# rpi_ad7705-2.net
KiCad netlist of a schematic drawn in EAGLE
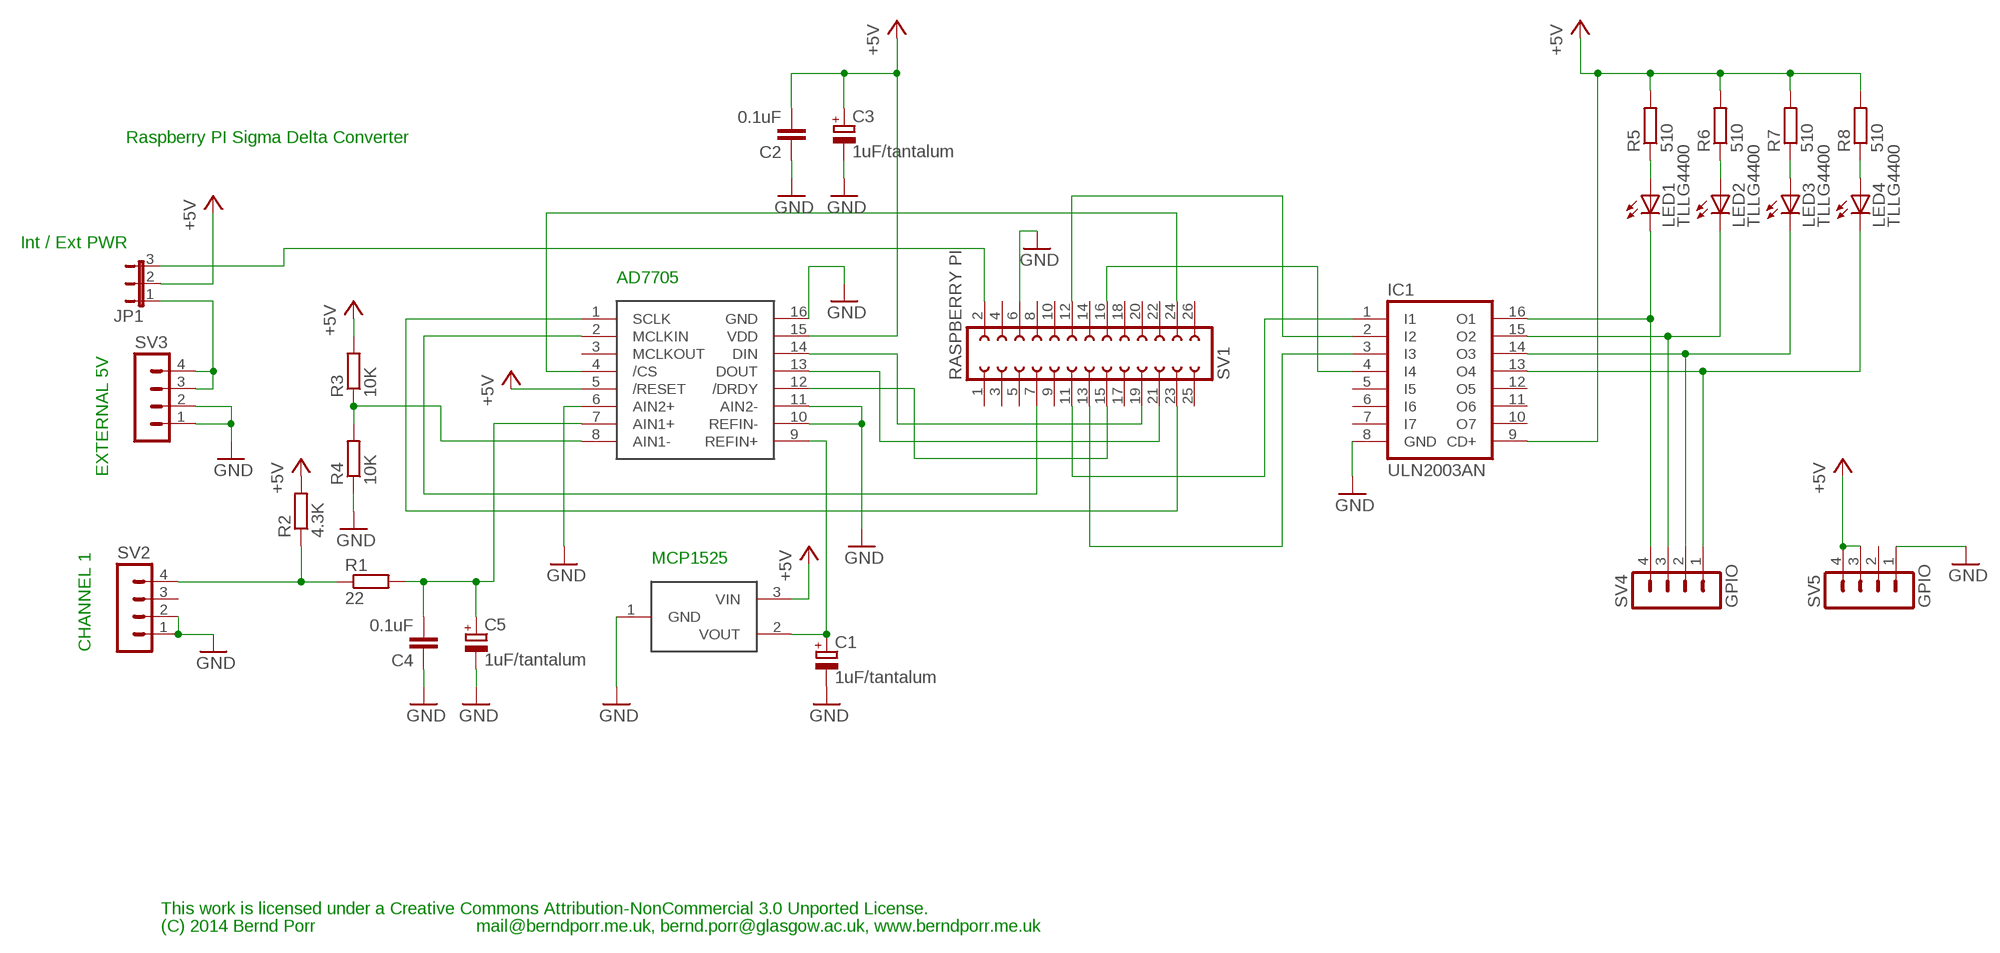
[diagram p0: schematic, sheet 1]

(export (version "E")
  (design (tool "Eeschema 10.0.6"))
  (components
    (comp (ref "C1")
      (value "1uF/tantalum")
      (footprint "eagle-import:TT2D7")
      (libsource (lib "eagle-import") (part "CPOL-EUTT2D7"))
    )
    (comp (ref "C2")
      (value "0.1uF")
      (footprint "eagle-import:C5B2.5")
      (libsource (lib "eagle-import") (part "C5/2.5"))
    )
    (comp (ref "C3")
      (value "1uF/tantalum")
      (footprint "eagle-import:TT2D7")
      (libsource (lib "eagle-import") (part "CPOL-EUTT2D7"))
    )
    (comp (ref "C4")
      (value "0.1uF")
      (footprint "eagle-import:C5B2.5")
      (libsource (lib "eagle-import") (part "C5/2.5"))
    )
    (comp (ref "C5")
      (value "1uF/tantalum")
      (footprint "eagle-import:TT2D7")
      (libsource (lib "eagle-import") (part "CPOL-EUTT2D7"))
    )
    (comp (ref "IC1")
      (value "ULN2003AN")
      (footprint "eagle-import:DIL16")
      (libsource (lib "eagle-import") (part "ULN2003AN"))
    )
    (comp (ref "JP1")
      (value "JP2E")
      (footprint "eagle-import:JP2")
      (libsource (lib "eagle-import") (part "JP2E"))
    )
    (comp (ref "LED1")
      (value "TLLG4400")
      (footprint "eagle-import:LED3MM")
      (fields (field (name "MF") "VISHAY SEMICONDUCTOR"))
      (libsource (lib "eagle-import") (part "TLLG4400"))
    )
    (comp (ref "LED2")
      (value "TLLG4400")
      (footprint "eagle-import:LED3MM")
      (fields (field (name "MF") "VISHAY SEMICONDUCTOR"))
      (libsource (lib "eagle-import") (part "TLLG4400"))
    )
    (comp (ref "LED3")
      (value "TLLG4400")
      (footprint "eagle-import:LED3MM")
      (fields (field (name "MF") "VISHAY SEMICONDUCTOR"))
      (libsource (lib "eagle-import") (part "TLLG4400"))
    )
    (comp (ref "LED4")
      (value "TLLG4400")
      (footprint "eagle-import:LED3MM")
      (fields (field (name "MF") "VISHAY SEMICONDUCTOR"))
      (libsource (lib "eagle-import") (part "TLLG4400"))
    )
    (comp (ref "R1")
      (value "22")
      (footprint "eagle-import:0207_10")
      (libsource (lib "eagle-import") (part "R-EU_0207/10"))
    )
    (comp (ref "R2")
      (value "4.3K")
      (footprint "eagle-import:0207_10")
      (libsource (lib "eagle-import") (part "R-EU_0207/10"))
    )
    (comp (ref "R3")
      (value "10K")
      (footprint "eagle-import:0207_10")
      (libsource (lib "eagle-import") (part "R-EU_0207/10"))
    )
    (comp (ref "R4")
      (value "10K")
      (footprint "eagle-import:0207_10")
      (libsource (lib "eagle-import") (part "R-EU_0207/10"))
    )
    (comp (ref "R5")
      (value "510")
      (footprint "eagle-import:0207_10")
      (libsource (lib "eagle-import") (part "R-EU_0207/10"))
    )
    (comp (ref "R6")
      (value "510")
      (footprint "eagle-import:0207_10")
      (libsource (lib "eagle-import") (part "R-EU_0207/10"))
    )
    (comp (ref "R7")
      (value "510")
      (footprint "eagle-import:0207_10")
      (libsource (lib "eagle-import") (part "R-EU_0207/10"))
    )
    (comp (ref "R8")
      (value "510")
      (footprint "eagle-import:0207_10")
      (libsource (lib "eagle-import") (part "R-EU_0207/10"))
    )
    (comp (ref "SV1")
      (value "RASPBERRY PI")
      (footprint "eagle-import:FE13-2")
      (libsource (lib "eagle-import") (part "FE13-2"))
    )
    (comp (ref "SV2")
      (value "MA04-1")
      (footprint "eagle-import:MA04-1")
      (libsource (lib "eagle-import") (part "MA04-1"))
    )
    (comp (ref "SV3")
      (value "MA04-1")
      (footprint "eagle-import:MA04-1")
      (libsource (lib "eagle-import") (part "MA04-1"))
    )
    (comp (ref "SV4")
      (value "GPIO")
      (footprint "eagle-import:MA04-1")
      (libsource (lib "eagle-import") (part "MA04-1"))
    )
    (comp (ref "SV5")
      (value "GPIO")
      (footprint "eagle-import:MA04-1")
      (libsource (lib "eagle-import") (part "MA04-1"))
    )
    (comp (ref "U$1")
      (value "AD7705")
      (footprint "eagle-import:DIP16")
      (libsource (lib "eagle-import") (part "AD7705"))
    )
    (comp (ref "U$2")
      (value "MCP1525")
      (footprint "eagle-import:TO92")
      (libsource (lib "eagle-import") (part "MCP1525"))
    )
  )
  (nets
    (net (code "1") (name "+5V") (class "Default")
      (node (ref "C2") (pin "2") (pinfunction "2_2") (pintype "passive"))
      (node (ref "C3") (pin "+") (pinfunction "+_+") (pintype "passive"))
      (node (ref "IC1") (pin "9") (pinfunction "CD+_9") (pintype "passive"))
      (node (ref "JP1") (pin "2") (pinfunction "2_2") (pintype "passive"))
      (node (ref "R2") (pin "2") (pinfunction "2_2") (pintype "passive"))
      (node (ref "R3") (pin "2") (pinfunction "2_2") (pintype "passive"))
      (node (ref "R5") (pin "2") (pinfunction "2_2") (pintype "passive"))
      (node (ref "R6") (pin "2") (pinfunction "2_2") (pintype "passive"))
      (node (ref "R7") (pin "2") (pinfunction "2_2") (pintype "passive"))
      (node (ref "R8") (pin "2") (pinfunction "2_2") (pintype "passive"))
      (node (ref "SV5") (pin "3") (pinfunction "3_3") (pintype "passive"))
      (node (ref "SV5") (pin "4") (pinfunction "4_4") (pintype "passive"))
      (node (ref "U$1") (pin "15") (pinfunction "VDD_15") (pintype "power_in"))
      (node (ref "U$1") (pin "5") (pinfunction "/RESET_5") (pintype "bidirectional"))
      (node (ref "U$2") (pin "3") (pinfunction "VIN_3") (pintype "power_in"))
    )
    (net (code "2") (name "GND") (class "Default")
      (node (ref "C1") (pin "-") (pinfunction "-_-") (pintype "passive"))
      (node (ref "C2") (pin "1") (pinfunction "1_1") (pintype "passive"))
      (node (ref "C3") (pin "-") (pinfunction "-_-") (pintype "passive"))
      (node (ref "C4") (pin "1") (pinfunction "1_1") (pintype "passive"))
      (node (ref "C5") (pin "-") (pinfunction "-_-") (pintype "passive"))
      (node (ref "IC1") (pin "8") (pinfunction "GND_8") (pintype "power_in"))
      (node (ref "R4") (pin "1") (pinfunction "1_1") (pintype "passive"))
      (node (ref "SV1") (pin "6") (pinfunction "6_6") (pintype "passive"))
      (node (ref "SV2") (pin "1") (pinfunction "1_1") (pintype "passive"))
      (node (ref "SV2") (pin "2") (pinfunction "2_2") (pintype "passive"))
      (node (ref "SV3") (pin "1") (pinfunction "1_1") (pintype "passive"))
      (node (ref "SV3") (pin "2") (pinfunction "2_2") (pintype "passive"))
      (node (ref "SV5") (pin "1") (pinfunction "1_1") (pintype "passive"))
      (node (ref "U$1") (pin "10") (pinfunction "REFIN-_10") (pintype "bidirectional"))
      (node (ref "U$1") (pin "11") (pinfunction "AIN2-_11") (pintype "bidirectional"))
      (node (ref "U$1") (pin "16") (pinfunction "GND_16") (pintype "power_in"))
      (node (ref "U$1") (pin "6") (pinfunction "AIN2+_6") (pintype "bidirectional"))
      (node (ref "U$2") (pin "1") (pinfunction "GND_1") (pintype "power_in"))
    )
    (net (code "3") (name "Net-(IC1-I1)") (class "Default")
      (node (ref "IC1") (pin "1") (pinfunction "I1_1") (pintype "input"))
      (node (ref "SV1") (pin "11") (pinfunction "11_11") (pintype "passive"))
    )
    (net (code "4") (name "Net-(IC1-I2)") (class "Default")
      (node (ref "IC1") (pin "2") (pinfunction "I2_2") (pintype "input"))
      (node (ref "SV1") (pin "12") (pinfunction "12_12") (pintype "passive"))
    )
    (net (code "5") (name "Net-(IC1-I3)") (class "Default")
      (node (ref "IC1") (pin "3") (pinfunction "I3_3") (pintype "input"))
      (node (ref "SV1") (pin "13") (pinfunction "13_13") (pintype "passive"))
    )
    (net (code "6") (name "Net-(IC1-I4)") (class "Default")
      (node (ref "IC1") (pin "4") (pinfunction "I4_4") (pintype "input"))
      (node (ref "SV1") (pin "16") (pinfunction "16_16") (pintype "passive"))
    )
    (net (code "7") (name "Net-(IC1-O1)") (class "Default")
      (node (ref "IC1") (pin "16") (pinfunction "O1_16") (pintype "open_collector"))
      (node (ref "LED1") (pin "K") (pinfunction "C_K") (pintype "passive"))
      (node (ref "SV4") (pin "4") (pinfunction "4_4") (pintype "passive"))
    )
    (net (code "8") (name "Net-(IC1-O2)") (class "Default")
      (node (ref "IC1") (pin "15") (pinfunction "O2_15") (pintype "open_collector"))
      (node (ref "LED2") (pin "K") (pinfunction "C_K") (pintype "passive"))
      (node (ref "SV4") (pin "3") (pinfunction "3_3") (pintype "passive"))
    )
    (net (code "9") (name "Net-(IC1-O3)") (class "Default")
      (node (ref "IC1") (pin "14") (pinfunction "O3_14") (pintype "open_collector"))
      (node (ref "LED3") (pin "K") (pinfunction "C_K") (pintype "passive"))
      (node (ref "SV4") (pin "2") (pinfunction "2_2") (pintype "passive"))
    )
    (net (code "10") (name "Net-(IC1-O4)") (class "Default")
      (node (ref "IC1") (pin "13") (pinfunction "O4_13") (pintype "open_collector"))
      (node (ref "LED4") (pin "K") (pinfunction "C_K") (pintype "passive"))
      (node (ref "SV4") (pin "1") (pinfunction "1_1") (pintype "passive"))
    )
    (net (code "11") (name "Net-(JP1-Pad1)") (class "Default")
      (node (ref "JP1") (pin "1") (pinfunction "1_1") (pintype "passive"))
      (node (ref "SV3") (pin "3") (pinfunction "3_3") (pintype "passive"))
      (node (ref "SV3") (pin "4") (pinfunction "4_4") (pintype "passive"))
    )
    (net (code "12") (name "Net-(JP1-Pad3)") (class "Default")
      (node (ref "JP1") (pin "3") (pinfunction "3_3") (pintype "passive"))
      (node (ref "SV1") (pin "2") (pinfunction "2_2") (pintype "passive"))
    )
    (net (code "13") (name "Net-(LED1-PadA)") (class "Default")
      (node (ref "LED1") (pin "A") (pinfunction "A_A") (pintype "passive"))
      (node (ref "R5") (pin "1") (pinfunction "1_1") (pintype "passive"))
    )
    (net (code "14") (name "Net-(LED2-PadA)") (class "Default")
      (node (ref "LED2") (pin "A") (pinfunction "A_A") (pintype "passive"))
      (node (ref "R6") (pin "1") (pinfunction "1_1") (pintype "passive"))
    )
    (net (code "15") (name "Net-(LED3-PadA)") (class "Default")
      (node (ref "LED3") (pin "A") (pinfunction "A_A") (pintype "passive"))
      (node (ref "R7") (pin "1") (pinfunction "1_1") (pintype "passive"))
    )
    (net (code "16") (name "Net-(LED4-PadA)") (class "Default")
      (node (ref "LED4") (pin "A") (pinfunction "A_A") (pintype "passive"))
      (node (ref "R8") (pin "1") (pinfunction "1_1") (pintype "passive"))
    )
    (net (code "17") (name "Net-(R1-Pad1)") (class "Default")
      (node (ref "R1") (pin "1") (pinfunction "1_1") (pintype "passive"))
      (node (ref "R2") (pin "1") (pinfunction "1_1") (pintype "passive"))
      (node (ref "SV2") (pin "4") (pinfunction "4_4") (pintype "passive"))
    )
    (net (code "18") (name "Net-(U$1-AIN1+)") (class "Default")
      (node (ref "C4") (pin "2") (pinfunction "2_2") (pintype "passive"))
      (node (ref "C5") (pin "+") (pinfunction "+_+") (pintype "passive"))
      (node (ref "R1") (pin "2") (pinfunction "2_2") (pintype "passive"))
      (node (ref "U$1") (pin "7") (pinfunction "AIN1+_7") (pintype "bidirectional"))
    )
    (net (code "19") (name "Net-(U$1-AIN1-)") (class "Default")
      (node (ref "R3") (pin "1") (pinfunction "1_1") (pintype "passive"))
      (node (ref "R4") (pin "2") (pinfunction "2_2") (pintype "passive"))
      (node (ref "U$1") (pin "8") (pinfunction "AIN1-_8") (pintype "bidirectional"))
    )
    (net (code "20") (name "Net-(U$1-DIN)") (class "Default")
      (node (ref "SV1") (pin "19") (pinfunction "19_19") (pintype "passive"))
      (node (ref "U$1") (pin "14") (pinfunction "DIN_14") (pintype "bidirectional"))
    )
    (net (code "21") (name "Net-(U$1-DOUT)") (class "Default")
      (node (ref "SV1") (pin "21") (pinfunction "21_21") (pintype "passive"))
      (node (ref "U$1") (pin "13") (pinfunction "DOUT_13") (pintype "bidirectional"))
    )
    (net (code "22") (name "Net-(U$1-MCLKIN)") (class "Default")
      (node (ref "SV1") (pin "7") (pinfunction "7_7") (pintype "passive"))
      (node (ref "U$1") (pin "2") (pinfunction "MCLKIN_2") (pintype "bidirectional"))
    )
    (net (code "23") (name "Net-(U$1-REFIN+)") (class "Default")
      (node (ref "C1") (pin "+") (pinfunction "+_+") (pintype "passive"))
      (node (ref "U$1") (pin "9") (pinfunction "REFIN+_9") (pintype "bidirectional"))
      (node (ref "U$2") (pin "2") (pinfunction "VOUT_2") (pintype "power_in"))
    )
    (net (code "24") (name "Net-(U$1-SCLK)") (class "Default")
      (node (ref "SV1") (pin "23") (pinfunction "23_23") (pintype "passive"))
      (node (ref "U$1") (pin "1") (pinfunction "SCLK_1") (pintype "bidirectional"))
    )
    (net (code "25") (name "Net-(U$1-{slash}CS)") (class "Default")
      (node (ref "SV1") (pin "24") (pinfunction "24_24") (pintype "passive"))
      (node (ref "U$1") (pin "4") (pinfunction "/CS_4") (pintype "bidirectional"))
    )
    (net (code "26") (name "Net-(U$1-{slash}DRDY)") (class "Default")
      (node (ref "SV1") (pin "15") (pinfunction "15_15") (pintype "passive"))
      (node (ref "U$1") (pin "12") (pinfunction "/DRDY_12") (pintype "bidirectional"))
    )
    (net (code "27") (name "unconnected-(IC1-I5-Pad5)") (class "Default")
      (node (ref "IC1") (pin "5") (pinfunction "I5_5") (pintype "input"))
    )
    (net (code "28") (name "unconnected-(IC1-I6-Pad6)") (class "Default")
      (node (ref "IC1") (pin "6") (pinfunction "I6_6") (pintype "input"))
    )
    (net (code "29") (name "unconnected-(IC1-I7-Pad7)") (class "Default")
      (node (ref "IC1") (pin "7") (pinfunction "I7_7") (pintype "input"))
    )
    (net (code "30") (name "unconnected-(IC1-O5-Pad12)") (class "Default")
      (node (ref "IC1") (pin "12") (pinfunction "O5_12") (pintype "open_collector"))
    )
    (net (code "31") (name "unconnected-(IC1-O6-Pad11)") (class "Default")
      (node (ref "IC1") (pin "11") (pinfunction "O6_11") (pintype "open_collector"))
    )
    (net (code "32") (name "unconnected-(IC1-O7-Pad10)") (class "Default")
      (node (ref "IC1") (pin "10") (pinfunction "O7_10") (pintype "open_collector"))
    )
    (net (code "33") (name "unconnected-(SV1-Pad1)") (class "Default")
      (node (ref "SV1") (pin "1") (pinfunction "1_1") (pintype "passive"))
    )
    (net (code "34") (name "unconnected-(SV1-Pad3)") (class "Default")
      (node (ref "SV1") (pin "3") (pinfunction "3_3") (pintype "passive"))
    )
    (net (code "35") (name "unconnected-(SV1-Pad4)") (class "Default")
      (node (ref "SV1") (pin "4") (pinfunction "4_4") (pintype "passive"))
    )
    (net (code "36") (name "unconnected-(SV1-Pad5)") (class "Default")
      (node (ref "SV1") (pin "5") (pinfunction "5_5") (pintype "passive"))
    )
    (net (code "37") (name "unconnected-(SV1-Pad8)") (class "Default")
      (node (ref "SV1") (pin "8") (pinfunction "8_8") (pintype "passive"))
    )
    (net (code "38") (name "unconnected-(SV1-Pad9)") (class "Default")
      (node (ref "SV1") (pin "9") (pinfunction "9_9") (pintype "passive"))
    )
    (net (code "39") (name "unconnected-(SV1-Pad10)") (class "Default")
      (node (ref "SV1") (pin "10") (pinfunction "10_10") (pintype "passive"))
    )
    (net (code "40") (name "unconnected-(SV1-Pad14)") (class "Default")
      (node (ref "SV1") (pin "14") (pinfunction "14_14") (pintype "passive"))
    )
    (net (code "41") (name "unconnected-(SV1-Pad17)") (class "Default")
      (node (ref "SV1") (pin "17") (pinfunction "17_17") (pintype "passive"))
    )
    (net (code "42") (name "unconnected-(SV1-Pad18)") (class "Default")
      (node (ref "SV1") (pin "18") (pinfunction "18_18") (pintype "passive"))
    )
    (net (code "43") (name "unconnected-(SV1-Pad20)") (class "Default")
      (node (ref "SV1") (pin "20") (pinfunction "20_20") (pintype "passive"))
    )
    (net (code "44") (name "unconnected-(SV1-Pad22)") (class "Default")
      (node (ref "SV1") (pin "22") (pinfunction "22_22") (pintype "passive"))
    )
    (net (code "45") (name "unconnected-(SV1-Pad25)") (class "Default")
      (node (ref "SV1") (pin "25") (pinfunction "25_25") (pintype "passive"))
    )
    (net (code "46") (name "unconnected-(SV1-Pad26)") (class "Default")
      (node (ref "SV1") (pin "26") (pinfunction "26_26") (pintype "passive"))
    )
    (net (code "47") (name "unconnected-(SV2-Pad3)") (class "Default")
      (node (ref "SV2") (pin "3") (pinfunction "3_3") (pintype "passive"))
    )
    (net (code "48") (name "unconnected-(SV5-Pad2)") (class "Default")
      (node (ref "SV5") (pin "2") (pinfunction "2_2") (pintype "passive"))
    )
    (net (code "49") (name "unconnected-(U$1-MCLKOUT-Pad3)") (class "Default")
      (node (ref "U$1") (pin "3") (pinfunction "MCLKOUT_3") (pintype "bidirectional"))
    )
  )
)
